# Blink_Schematic_v2.net
KiCad netlist of a schematic drawn in EAGLE
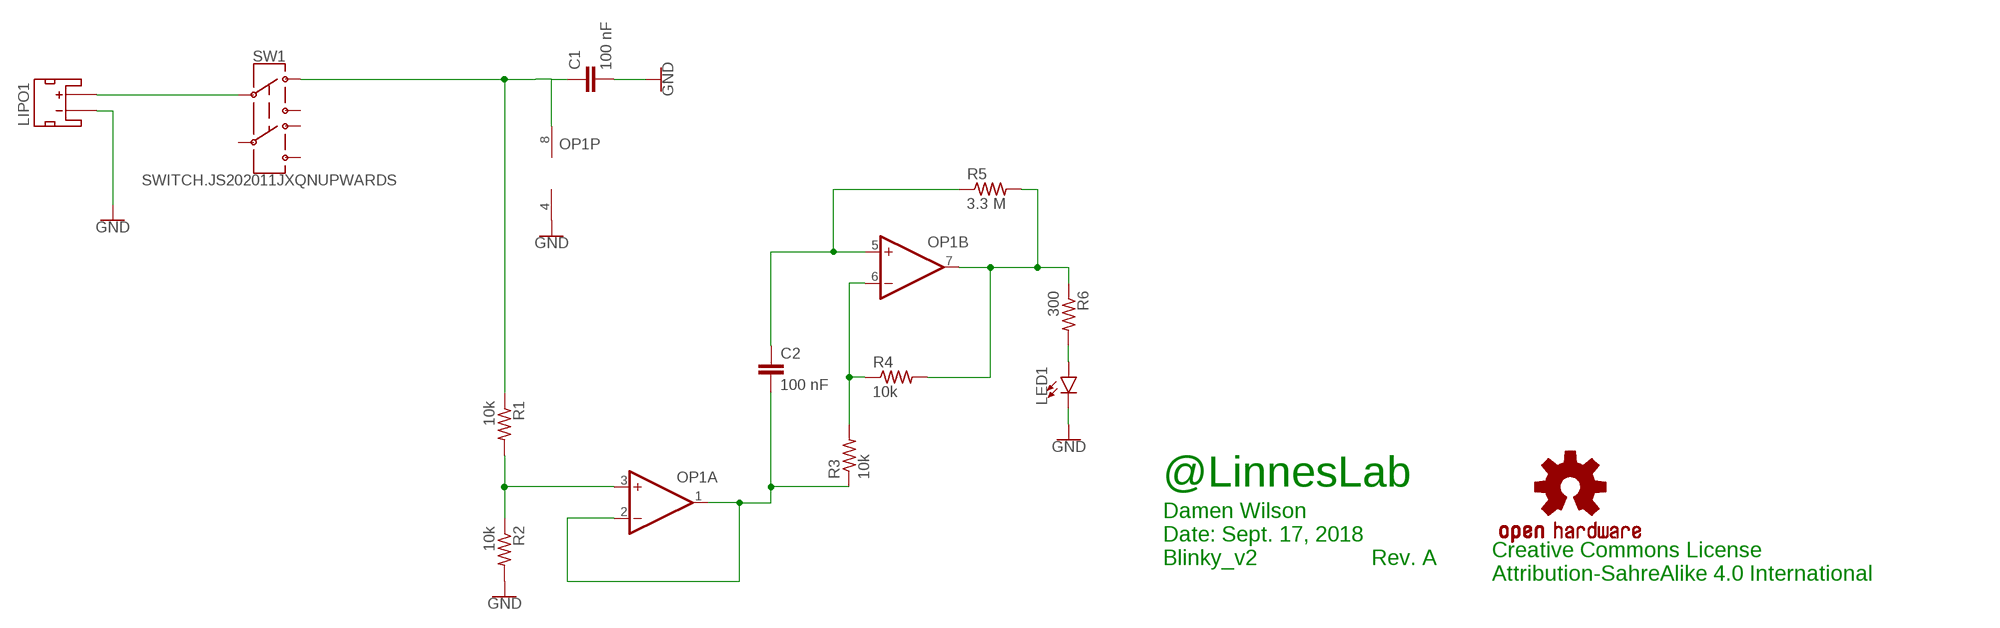
[diagram p0: schematic, sheet 1]

(export (version "E")
  (design (tool "Eeschema 10.0.6"))
  (components
    (comp (ref "C1")
      (value "100 nF")
      (footprint "eagle-import:C0402")
      (libsource (lib "eagle-import") (part "C-EUC0402"))
    )
    (comp (ref "C2")
      (value "100 nF")
      (footprint "eagle-import:C0402")
      (libsource (lib "eagle-import") (part "C-EUC0402"))
    )
    (comp (ref "LED1")
      (value "LED0603")
      (footprint "eagle-import:LED-0603")
      (libsource (lib "eagle-import") (part "LED0603"))
    )
    (comp (ref "LIPO1")
      (value "JST_2MM_MALE")
      (footprint "eagle-import:JST-2-SMD")
      (libsource (lib "eagle-import") (part "JST_2MM_MALE"))
    )
    (comp (ref "LOGO1")
      (value "OSHW-LOGOL")
      (footprint "eagle-import:OSHW-LOGO-L")
      (libsource (lib "eagle-import") (part "OSHW-LOGOL"))
    )
    (comp (ref "OP1")
      (value "OP-DUALRM")
      (footprint "eagle-import:MSOP08")
      (fields (field (name "MF") "ALTERA CORPORATION") (field (name "MPN") "AD8607ARMZ-REEL"))
      (libsource (lib "eagle-import") (part "OP-DUALRM"))
    )
    (comp (ref "R1")
      (value "10k")
      (footprint "eagle-import:R0402")
      (libsource (lib "eagle-import") (part "R-US_R0402"))
    )
    (comp (ref "R2")
      (value "10k")
      (footprint "eagle-import:R0402")
      (libsource (lib "eagle-import") (part "R-US_R0402"))
    )
    (comp (ref "R3")
      (value "10k")
      (footprint "eagle-import:R0402")
      (libsource (lib "eagle-import") (part "R-US_R0402"))
    )
    (comp (ref "R4")
      (value "10k")
      (footprint "eagle-import:R0402")
      (libsource (lib "eagle-import") (part "R-US_R0402"))
    )
    (comp (ref "R5")
      (value "3.3 M")
      (footprint "eagle-import:R0402")
      (libsource (lib "eagle-import") (part "R-US_R0402"))
    )
    (comp (ref "R6")
      (value "300")
      (footprint "eagle-import:R0402")
      (libsource (lib "eagle-import") (part "R-US_R0402"))
    )
    (comp (ref "SW1")
      (value "SWITCH.JS202011JXQNUPWARDS")
      (footprint "eagle-import:SWITCH.00")
      (libsource (lib "eagle-import") (part "SWITCH.JS202011JXQNUPWARDS"))
    )
  )
  (nets
    (net (code "1") (name "GND") (class "Default")
      (node (ref "C1") (pin "2") (pinfunction "2_2") (pintype "passive"))
      (node (ref "LED1") (pin "C") (pinfunction "C_C") (pintype "passive"))
      (node (ref "LIPO1") (pin "1") (pinfunction "-_1") (pintype "bidirectional"))
      (node (ref "OP1") (pin "4") (pinfunction "V-_4") (pintype "power_in"))
      (node (ref "R2") (pin "2") (pinfunction "2_2") (pintype "passive"))
    )
    (net (code "2") (name "Net-(LED1-PadA)") (class "Default")
      (node (ref "LED1") (pin "A") (pinfunction "A_A") (pintype "passive"))
      (node (ref "R6") (pin "2") (pinfunction "2_2") (pintype "passive"))
    )
    (net (code "3") (name "Net-(LIPO1-+)") (class "Default")
      (node (ref "LIPO1") (pin "2") (pinfunction "+_2") (pintype "bidirectional"))
      (node (ref "SW1") (pin "2") (pinfunction "2_2") (pintype "bidirectional"))
    )
    (net (code "4") (name "Net-(OP1A-+IN)") (class "Default")
      (node (ref "OP1") (pin "3") (pinfunction "+IN_3") (pintype "input"))
      (node (ref "R1") (pin "2") (pinfunction "2_2") (pintype "passive"))
      (node (ref "R2") (pin "1") (pinfunction "1_1") (pintype "passive"))
    )
    (net (code "5") (name "Net-(OP1A--IN)") (class "Default")
      (node (ref "C2") (pin "2") (pinfunction "2_2") (pintype "passive"))
      (node (ref "OP1") (pin "1") (pinfunction "OUT_1") (pintype "output"))
      (node (ref "OP1") (pin "2") (pinfunction "-IN_2") (pintype "input"))
      (node (ref "R3") (pin "1") (pinfunction "1_1") (pintype "passive"))
    )
    (net (code "6") (name "Net-(OP1B-+IN)") (class "Default")
      (node (ref "C2") (pin "1") (pinfunction "1_1") (pintype "passive"))
      (node (ref "OP1") (pin "5") (pinfunction "+IN_5") (pintype "input"))
      (node (ref "R5") (pin "1") (pinfunction "1_1") (pintype "passive"))
    )
    (net (code "7") (name "Net-(OP1B--IN)") (class "Default")
      (node (ref "OP1") (pin "6") (pinfunction "-IN_6") (pintype "input"))
      (node (ref "R3") (pin "2") (pinfunction "2_2") (pintype "passive"))
      (node (ref "R4") (pin "1") (pinfunction "1_1") (pintype "passive"))
    )
    (net (code "8") (name "Net-(OP1B-OUT)") (class "Default")
      (node (ref "OP1") (pin "7") (pinfunction "OUT_7") (pintype "output"))
      (node (ref "R4") (pin "2") (pinfunction "2_2") (pintype "passive"))
      (node (ref "R5") (pin "2") (pinfunction "2_2") (pintype "passive"))
      (node (ref "R6") (pin "1") (pinfunction "1_1") (pintype "passive"))
    )
    (net (code "9") (name "Net-(OP1C-V+)") (class "Default")
      (node (ref "C1") (pin "1") (pinfunction "1_1") (pintype "passive"))
      (node (ref "OP1") (pin "8") (pinfunction "V+_8") (pintype "power_in"))
      (node (ref "R1") (pin "1") (pinfunction "1_1") (pintype "passive"))
      (node (ref "SW1") (pin "1") (pinfunction "1_1") (pintype "bidirectional"))
    )
    (net (code "10") (name "unconnected-(LIPO1-PAD1-PadNC1)") (class "Default")
      (node (ref "LIPO1") (pin "NC1") (pinfunction "PAD1_NC1") (pintype "bidirectional"))
    )
    (net (code "11") (name "unconnected-(LIPO1-PAD2-PadNC2)") (class "Default")
      (node (ref "LIPO1") (pin "NC2") (pinfunction "PAD2_NC2") (pintype "bidirectional"))
    )
    (net (code "12") (name "unconnected-(SW1-Pad3)") (class "Default")
      (node (ref "SW1") (pin "3") (pinfunction "3_3") (pintype "bidirectional"))
    )
    (net (code "13") (name "unconnected-(SW1-Pad5)") (class "Default")
      (node (ref "SW1") (pin "5") (pinfunction "5_5") (pintype "bidirectional"))
    )
    (net (code "14") (name "unconnected-(SW1-Pad6)") (class "Default")
      (node (ref "SW1") (pin "6") (pinfunction "6_6") (pintype "bidirectional"))
    )
    (net (code "15") (name "unconnected-(SW1-Pad7)") (class "Default")
      (node (ref "SW1") (pin "7") (pinfunction "7_7") (pintype "bidirectional"))
    )
  )
)
